# CAN.net
KiCad netlist of a schematic drawn in Altium Designer
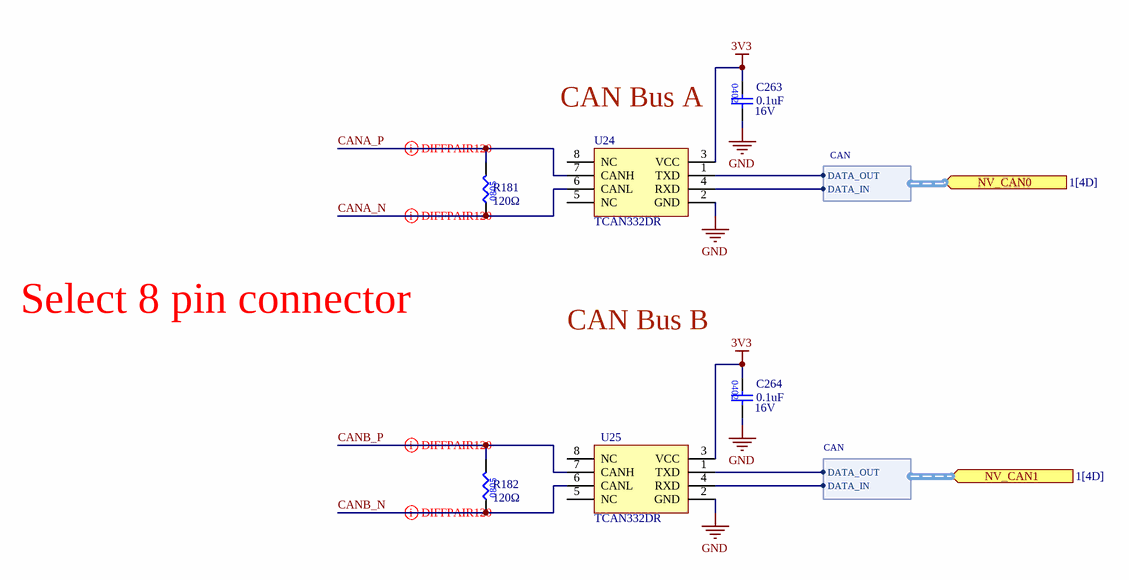
[diagram p0: CAN.SchDoc]

(export (version "E")
  (design (tool "Eeschema 10.0.6"))
  (components
    (comp (ref "C263")
      (value "CAP_0.1uF_16V_X7R_0402")
      (footprint "CAP0402")
      (description "CAP CER 0.1UF 16V X7R 0402")
      (fields (field (name "CAPACITANCE") "0.1uF") (field (name "VOLTAGE RATING") "16V"))
      (libsource (lib "UWRT_Schematic_Library_2020") (part "CAP_0.1uF_16V_X7R_0402"))
    )
    (comp (ref "C264")
      (value "CAP_0.1uF_16V_X7R_0402")
      (footprint "CAP0402")
      (description "CAP CER 0.1UF 16V X7R 0402")
      (fields (field (name "CAPACITANCE") "0.1uF") (field (name "VOLTAGE RATING") "16V"))
      (libsource (lib "UWRT_Schematic_Library_2020") (part "CAP_0.1uF_16V_X7R_0402"))
    )
    (comp (ref "R181")
      (value "120Ω")
      (footprint "RES0805")
      (description "RES 120 OHM 1% 1/8W 0805")
      (fields (field (name "LCSC PART #") "C17437") (field (name "Comment") "RES_120Ω_0805_1%"))
      (libsource (lib "UWRT_Schematic_Library_2020") (part "RES_120Ω_0805_1%"))
    )
    (comp (ref "R182")
      (value "120Ω")
      (footprint "RES0805")
      (description "RES 120 OHM 1% 1/8W 0805")
      (fields (field (name "LCSC PART #") "C17437") (field (name "Comment") "RES_120Ω_0805_1%"))
      (libsource (lib "UWRT_Schematic_Library_2020") (part "RES_120Ω_0805_1%"))
    )
    (comp (ref "U24")
      (value "TCAN332DR")
      (footprint "SOIC127P599X175-8N")
      (description "IC CAN TRANSCEIVER")
      (fields (field (name "MANUFACTURER PART NUMBER 1") "TCAN332DR"))
      (libsource (lib "UWRT_Schematic_Library_2020") (part "TCAN332DR"))
    )
    (comp (ref "U25")
      (value "TCAN332DR")
      (footprint "SOIC127P599X175-8N")
      (description "IC CAN TRANSCEIVER")
      (fields (field (name "MANUFACTURER PART NUMBER 1") "TCAN332DR"))
      (libsource (lib "UWRT_Schematic_Library_2020") (part "TCAN332DR"))
    )
  )
  (nets
    (net (code "2") (name "/CANA_N") (class "Default")
      (node (ref "R181") (pin "1") (pinfunction "1_1") (pintype "passive"))
      (node (ref "U24") (pin "6") (pinfunction "CANL_6") (pintype "passive"))
    )
    (net (code "3") (name "/CANA_P") (class "Default")
      (node (ref "R181") (pin "2") (pinfunction "2_2") (pintype "passive"))
      (node (ref "U24") (pin "7") (pinfunction "CANH_7") (pintype "passive"))
    )
    (net (code "4") (name "/CANB_N") (class "Default")
      (node (ref "R182") (pin "1") (pinfunction "1_1") (pintype "passive"))
      (node (ref "U25") (pin "6") (pinfunction "CANL_6") (pintype "passive"))
    )
    (net (code "5") (name "/CANB_P") (class "Default")
      (node (ref "R182") (pin "2") (pinfunction "2_2") (pintype "passive"))
      (node (ref "U25") (pin "7") (pinfunction "CANH_7") (pintype "passive"))
    )
    (net (code "7") (name "3V3") (class "Default")
      (node (ref "C263") (pin "1") (pinfunction "1_1") (pintype "passive"))
      (node (ref "C264") (pin "1") (pinfunction "1_1") (pintype "passive"))
      (node (ref "U24") (pin "3") (pinfunction "VCC_3") (pintype "passive"))
      (node (ref "U25") (pin "3") (pinfunction "VCC_3") (pintype "passive"))
    )
    (net (code "8") (name "GND") (class "Default")
      (node (ref "C263") (pin "2") (pinfunction "2_2") (pintype "passive"))
      (node (ref "C264") (pin "2") (pinfunction "2_2") (pintype "passive"))
      (node (ref "U24") (pin "2") (pinfunction "GND_2") (pintype "passive"))
      (node (ref "U25") (pin "2") (pinfunction "GND_2") (pintype "passive"))
    )
    (net (code "9") (name "unconnected-(U24-NC-Pad5)") (class "Default")
      (node (ref "U24") (pin "5") (pinfunction "NC_5") (pintype "passive"))
    )
    (net (code "10") (name "unconnected-(U24-NC-Pad8)") (class "Default")
      (node (ref "U24") (pin "8") (pinfunction "NC_8") (pintype "passive"))
    )
    (net (code "11") (name "unconnected-(U24-RXD-Pad4)") (class "Default")
      (node (ref "U24") (pin "4") (pinfunction "RXD_4") (pintype "passive"))
    )
    (net (code "12") (name "unconnected-(U24-TXD-Pad1)") (class "Default")
      (node (ref "U24") (pin "1") (pinfunction "TXD_1") (pintype "passive"))
    )
    (net (code "13") (name "unconnected-(U25-NC-Pad5)") (class "Default")
      (node (ref "U25") (pin "5") (pinfunction "NC_5") (pintype "passive"))
    )
    (net (code "14") (name "unconnected-(U25-NC-Pad8)") (class "Default")
      (node (ref "U25") (pin "8") (pinfunction "NC_8") (pintype "passive"))
    )
    (net (code "15") (name "unconnected-(U25-RXD-Pad4)") (class "Default")
      (node (ref "U25") (pin "4") (pinfunction "RXD_4") (pintype "passive"))
    )
    (net (code "16") (name "unconnected-(U25-TXD-Pad1)") (class "Default")
      (node (ref "U25") (pin "1") (pinfunction "TXD_1") (pintype "passive"))
    )
  )
)
